# RS232.net
KiCad netlist of a schematic drawn in Altium Designer
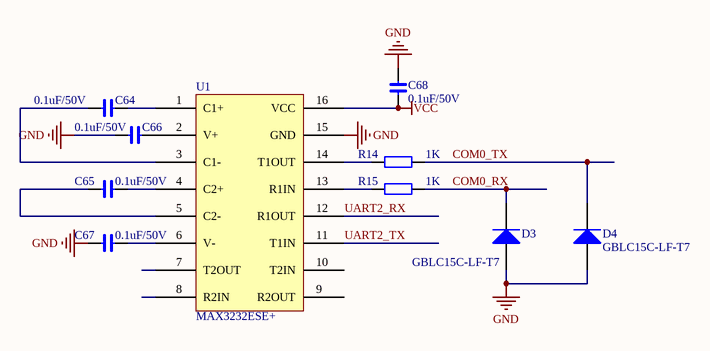
[diagram p0: RS232.SchDoc]

(export (version "E")
  (design (tool "Eeschema 10.0.6"))
  (components
    (comp (ref "C64")
      (value "0.1uF/50V")
      (footprint "0402C")
      (description "C")
      (libsource (lib "Top") (part "C"))
    )
    (comp (ref "C65")
      (value "0.1uF/50V")
      (footprint "0402C")
      (description "C")
      (libsource (lib "Top") (part "C"))
    )
    (comp (ref "C66")
      (value "0.1uF/50V")
      (footprint "0402C")
      (description "C")
      (libsource (lib "Top") (part "C"))
    )
    (comp (ref "C67")
      (value "0.1uF/50V")
      (footprint "0402C")
      (description "C")
      (libsource (lib "Top") (part "C"))
    )
    (comp (ref "C68")
      (value "0.1uF/50V")
      (footprint "0402C")
      (description "C")
      (libsource (lib "Top") (part "C"))
    )
    (comp (ref "D3")
      (value "GBLC15C-LF-T7")
      (footprint "SOD323")
      (description "Default Diode")
      (fields (field (name "PUBLISHER") "Altium Limited"))
      (libsource (lib "Miscellaneous Devices") (part "Diode"))
    )
    (comp (ref "D4")
      (value "GBLC15C-LF-T7")
      (footprint "SOD323")
      (description "Default Diode")
      (fields (field (name "PUBLISHER") "Altium Limited"))
      (libsource (lib "Miscellaneous Devices") (part "Diode"))
    )
    (comp (ref "R14")
      (value "1K")
      (footprint "0402R")
      (description "Resistor")
      (fields (field (name "PUBLISHER") "Altium Limited"))
      (libsource (lib "Miscellaneous Devices") (part "Res2"))
    )
    (comp (ref "R15")
      (value "1K")
      (footprint "0402R")
      (description "Resistor")
      (fields (field (name "PUBLISHER") "Altium Limited"))
      (libsource (lib "Miscellaneous Devices") (part "Res2"))
    )
    (comp (ref "U1")
      (value "MAX3232ESE+")
      (footprint "SOIC127P600X265-16N")
      (libsource (lib "Schlib_20110825") (part "MAX3232ESE+"))
    )
  )
  (nets
    (net (code "1") (name "/COM0_RX") (class "Default")
      (node (ref "D3") (pin "K") (pinfunction "K_K") (pintype "passive"))
      (node (ref "R15") (pin "1") (pinfunction "1_1") (pintype "passive"))
    )
    (net (code "2") (name "/COM0_TX") (class "Default")
      (node (ref "D4") (pin "K") (pinfunction "K_K") (pintype "passive"))
      (node (ref "R14") (pin "1") (pinfunction "1_1") (pintype "passive"))
    )
    (net (code "3") (name "/UART2_RX") (class "Default")
      (node (ref "U1") (pin "12") (pinfunction "R1OUT_12") (pintype "passive"))
    )
    (net (code "4") (name "/UART2_TX") (class "Default")
      (node (ref "U1") (pin "11") (pinfunction "T1IN_11") (pintype "passive"))
    )
    (net (code "5") (name "GND") (class "Default")
      (node (ref "C66") (pin "2") (pintype "passive"))
      (node (ref "C67") (pin "2") (pintype "passive"))
      (node (ref "C68") (pin "1") (pintype "passive"))
      (node (ref "D3") (pin "A") (pinfunction "A_A") (pintype "passive"))
      (node (ref "D4") (pin "A") (pinfunction "A_A") (pintype "passive"))
      (node (ref "U1") (pin "15") (pinfunction "GND_15") (pintype "passive"))
    )
    (net (code "6") (name "Net-(U1-C1+)") (class "Default")
      (node (ref "C64") (pin "1") (pintype "passive"))
      (node (ref "U1") (pin "1") (pinfunction "C1+_1") (pintype "passive"))
    )
    (net (code "7") (name "Net-(U1-C1-)") (class "Default")
      (node (ref "C64") (pin "2") (pintype "passive"))
      (node (ref "U1") (pin "3") (pinfunction "C1-_3") (pintype "passive"))
    )
    (net (code "8") (name "Net-(U1-C2+)") (class "Default")
      (node (ref "C65") (pin "1") (pintype "passive"))
      (node (ref "U1") (pin "4") (pinfunction "C2+_4") (pintype "passive"))
    )
    (net (code "9") (name "Net-(U1-C2-)") (class "Default")
      (node (ref "C65") (pin "2") (pintype "passive"))
      (node (ref "U1") (pin "5") (pinfunction "C2-_5") (pintype "passive"))
    )
    (net (code "10") (name "Net-(U1-R1IN)") (class "Default")
      (node (ref "R15") (pin "2") (pinfunction "2_2") (pintype "passive"))
      (node (ref "U1") (pin "13") (pinfunction "R1IN_13") (pintype "passive"))
    )
    (net (code "11") (name "Net-(U1-T1OUT)") (class "Default")
      (node (ref "R14") (pin "2") (pinfunction "2_2") (pintype "passive"))
      (node (ref "U1") (pin "14") (pinfunction "T1OUT_14") (pintype "passive"))
    )
    (net (code "12") (name "Net-(U1-V+)") (class "Default")
      (node (ref "C66") (pin "1") (pintype "passive"))
      (node (ref "U1") (pin "2") (pinfunction "V+_2") (pintype "passive"))
    )
    (net (code "13") (name "Net-(U1-V-)") (class "Default")
      (node (ref "C67") (pin "1") (pintype "passive"))
      (node (ref "U1") (pin "6") (pinfunction "V-_6") (pintype "passive"))
    )
    (net (code "14") (name "VCC") (class "Default")
      (node (ref "C68") (pin "2") (pintype "passive"))
      (node (ref "U1") (pin "16") (pinfunction "VCC_16") (pintype "passive"))
    )
    (net (code "15") (name "unconnected-(U1-R2IN-Pad8)") (class "Default")
      (node (ref "U1") (pin "8") (pinfunction "R2IN_8") (pintype "passive"))
    )
    (net (code "16") (name "unconnected-(U1-R2OUT-Pad9)") (class "Default")
      (node (ref "U1") (pin "9") (pinfunction "R2OUT_9") (pintype "passive"))
    )
    (net (code "17") (name "unconnected-(U1-T2IN-Pad10)") (class "Default")
      (node (ref "U1") (pin "10") (pinfunction "T2IN_10") (pintype "passive"))
    )
    (net (code "18") (name "unconnected-(U1-T2OUT-Pad7)") (class "Default")
      (node (ref "U1") (pin "7") (pinfunction "T2OUT_7") (pintype "passive"))
    )
  )
)
